# untitled2-6-2.net
KiCad netlist of a schematic drawn in EAGLE
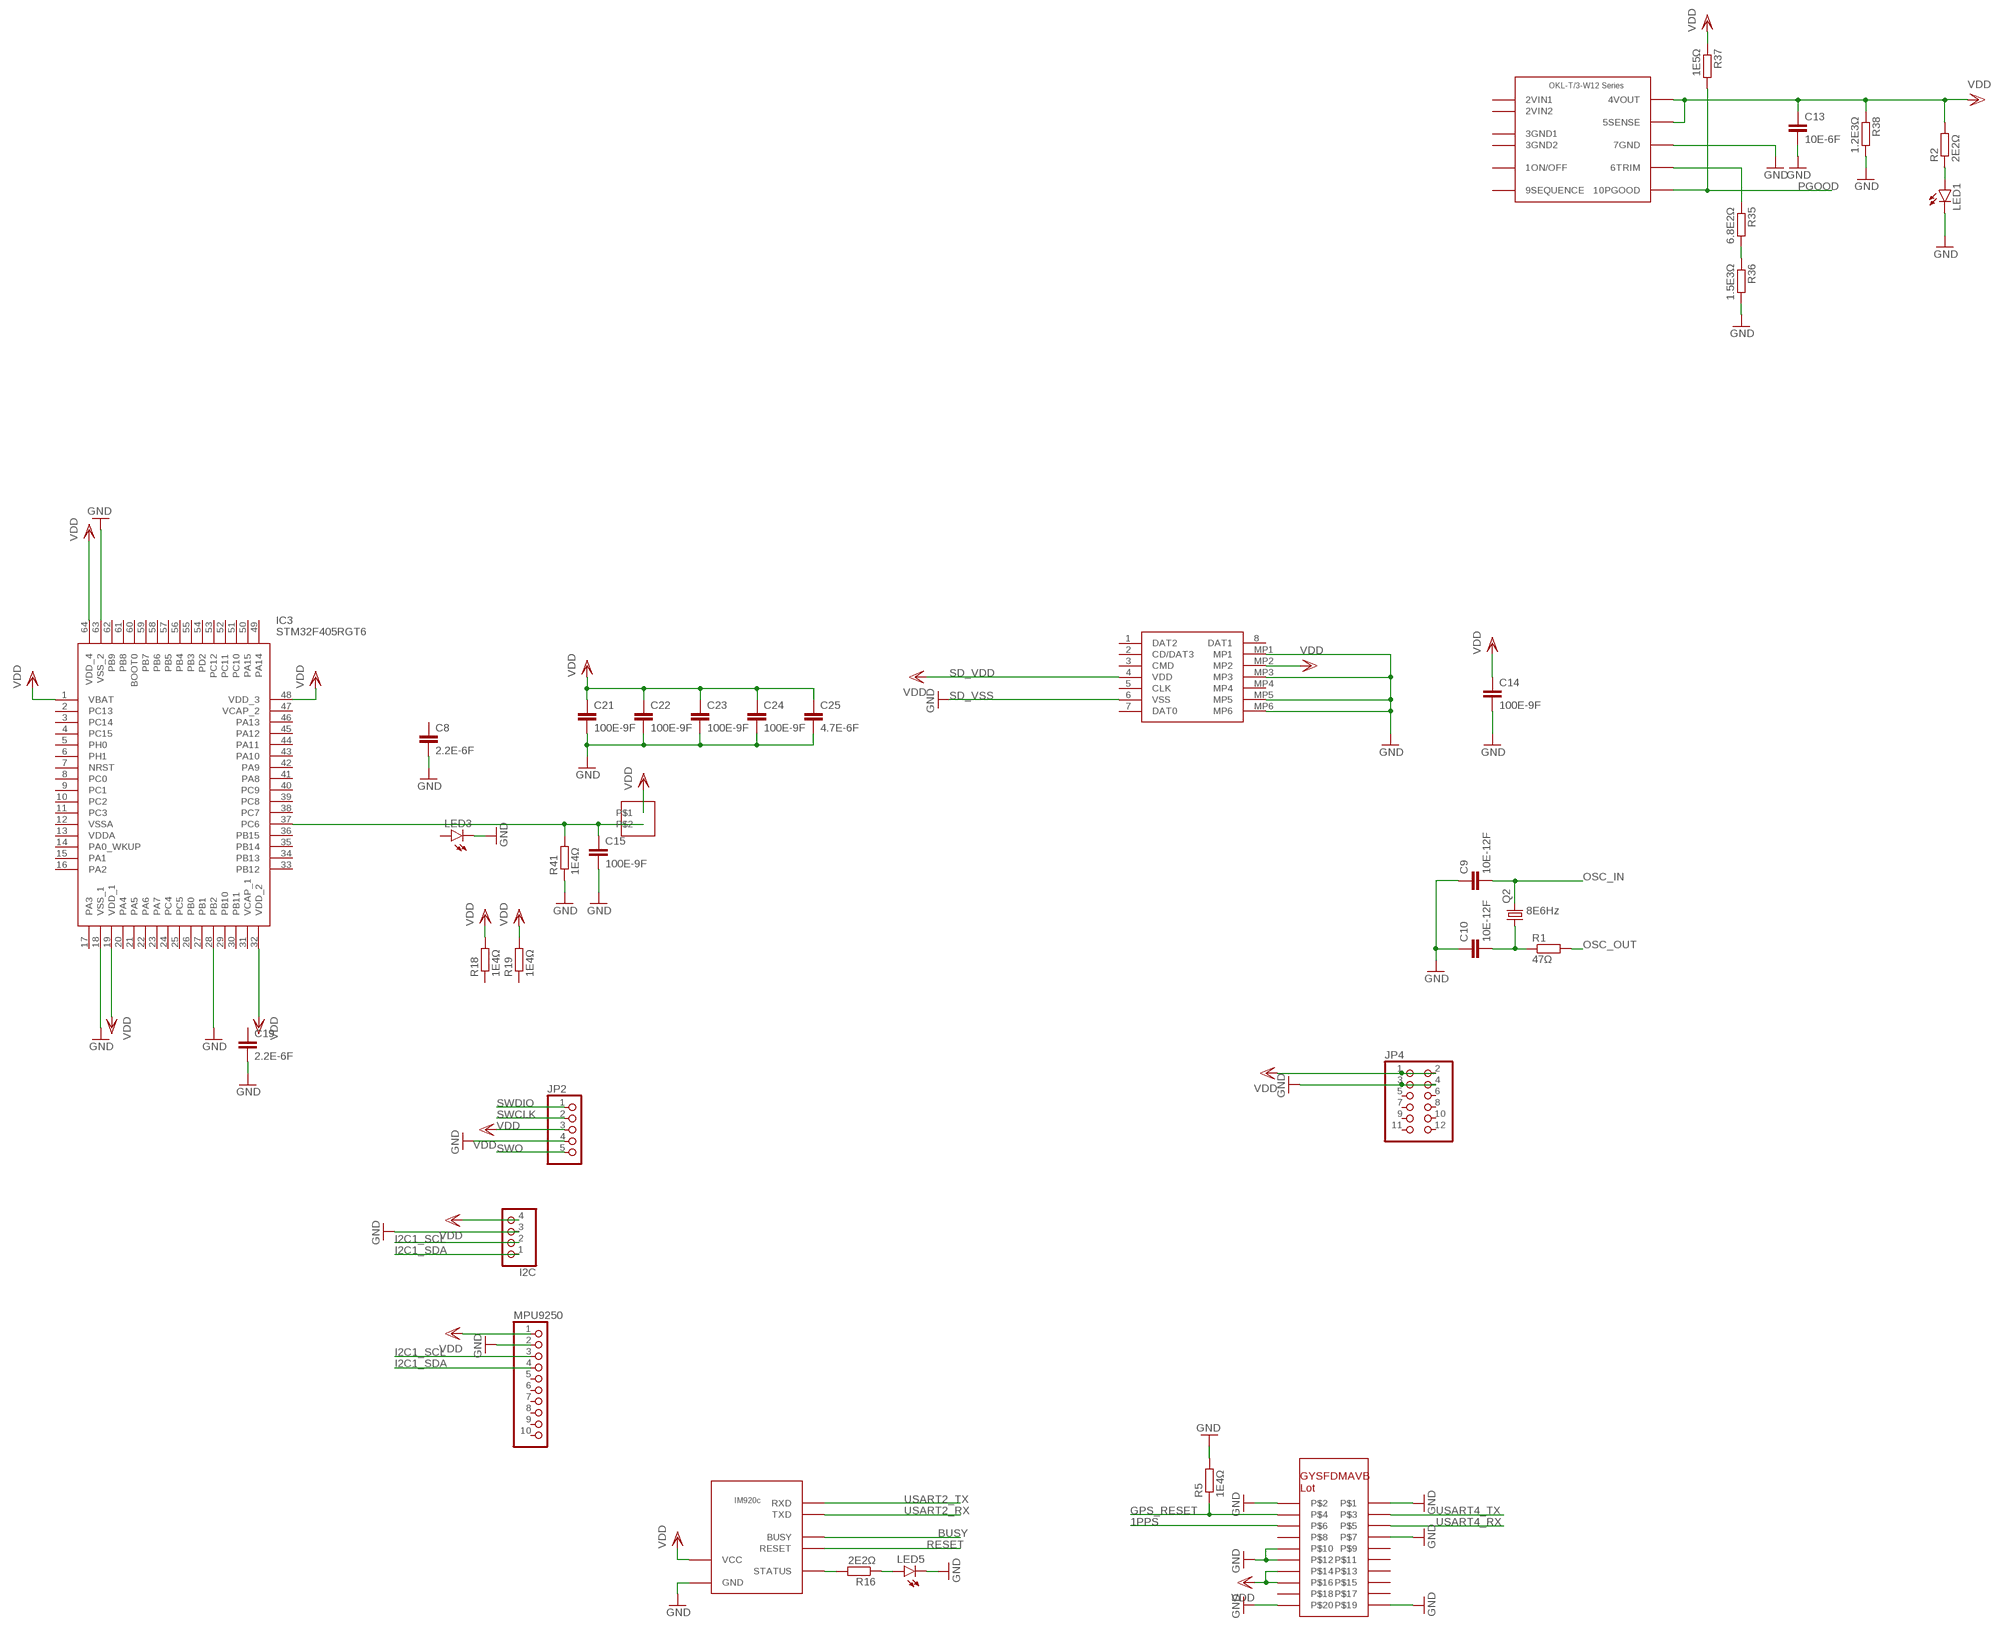
[diagram p0: schematic, sheet 1]

(export (version "E")
  (design (tool "Eeschema 10.0.6"))
  (components
    (comp (ref "C8")
      (value "2.2E-6F")
      (footprint "eagle-import:C0805")
      (libsource (lib "eagle-import") (part "C-EUC0805"))
    )
    (comp (ref "C9")
      (value "10E-12F")
      (footprint "eagle-import:C0805")
      (libsource (lib "eagle-import") (part "C-EUC0805"))
    )
    (comp (ref "C10")
      (value "10E-12F")
      (footprint "eagle-import:C0805")
      (libsource (lib "eagle-import") (part "C-EUC0805"))
    )
    (comp (ref "C13")
      (value "10E-6F")
      (footprint "eagle-import:C0805")
      (libsource (lib "eagle-import") (part "C-EUC0805"))
    )
    (comp (ref "C14")
      (value "100E-9F")
      (footprint "eagle-import:C0805")
      (libsource (lib "eagle-import") (part "C-EUC0805"))
    )
    (comp (ref "C15")
      (value "100E-9F")
      (footprint "eagle-import:C0805")
      (libsource (lib "eagle-import") (part "C-EUC0805"))
    )
    (comp (ref "C19")
      (value "2.2E-6F")
      (footprint "eagle-import:C0805")
      (libsource (lib "eagle-import") (part "C-EUC0805"))
    )
    (comp (ref "C21")
      (value "100E-9F")
      (footprint "eagle-import:C0805")
      (libsource (lib "eagle-import") (part "C-EUC0805"))
    )
    (comp (ref "C22")
      (value "100E-9F")
      (footprint "eagle-import:C0805")
      (libsource (lib "eagle-import") (part "C-EUC0805"))
    )
    (comp (ref "C23")
      (value "100E-9F")
      (footprint "eagle-import:C0805")
      (libsource (lib "eagle-import") (part "C-EUC0805"))
    )
    (comp (ref "C24")
      (value "100E-9F")
      (footprint "eagle-import:C0805")
      (libsource (lib "eagle-import") (part "C-EUC0805"))
    )
    (comp (ref "C25")
      (value "4.7E-6F")
      (footprint "eagle-import:C0805")
      (libsource (lib "eagle-import") (part "C-EUC0805"))
    )
    (comp (ref "I2C")
      (value "PINHD-1X4")
      (footprint "eagle-import:1X04")
      (libsource (lib "eagle-import") (part "PINHD-1X4"))
    )
    (comp (ref "IC3")
      (value "STM32F405RGT6")
      (footprint "eagle-import:QFP50P1200X1200X160-64N")
      (fields (field (name "MOUSER_PART_NUMBER") "511-STM32F405RGT6"))
      (libsource (lib "eagle-import") (part "STM32F405RGT6"))
    )
    (comp (ref "J1")
      (value "DM3AT-SF-PEJM5")
      (footprint "eagle-import:DM3ATSFPEJM5")
      (fields (field (name "MOUSER_PART_NUMBER") "798-DM3AT-SF-PEJM5"))
      (libsource (lib "eagle-import") (part "DM3AT-SF-PEJM5"))
    )
    (comp (ref "JP2")
      (value "PINHD-1X5")
      (footprint "eagle-import:1X05")
      (libsource (lib "eagle-import") (part "PINHD-1X5"))
    )
    (comp (ref "JP4")
      (value "PINHD-2X6")
      (footprint "eagle-import:2X06")
      (libsource (lib "eagle-import") (part "PINHD-2X6"))
    )
    (comp (ref "LED1")
      (value "LEDCHIP-LED0805")
      (footprint "eagle-import:CHIP-LED0805")
      (libsource (lib "eagle-import") (part "LEDCHIP-LED0805"))
    )
    (comp (ref "LED3")
      (value "LEDCHIP-LED0805")
      (footprint "eagle-import:CHIP-LED0805")
      (libsource (lib "eagle-import") (part "LEDCHIP-LED0805"))
    )
    (comp (ref "LED5")
      (value "LEDCHIP-LED0805")
      (footprint "eagle-import:CHIP-LED0805")
      (libsource (lib "eagle-import") (part "LEDCHIP-LED0805"))
    )
    (comp (ref "MPU9250")
      (value "PINHD-1X10")
      (footprint "eagle-import:1X10")
      (libsource (lib "eagle-import") (part "PINHD-1X10"))
    )
    (comp (ref "Q2")
      (value "CRYSTALCTS406")
      (footprint "eagle-import:CTS406")
      (libsource (lib "eagle-import") (part "CRYSTALCTS406"))
    )
    (comp (ref "R1")
      (value "47Ω")
      (footprint "eagle-import:R0603")
      (libsource (lib "eagle-import") (part "R-EU_R0603"))
    )
    (comp (ref "R2")
      (value "2E2Ω")
      (footprint "eagle-import:R0603")
      (libsource (lib "eagle-import") (part "R-EU_R0603"))
    )
    (comp (ref "R5")
      (value "1E4Ω")
      (footprint "eagle-import:R0603")
      (libsource (lib "eagle-import") (part "R-EU_R0603"))
    )
    (comp (ref "R16")
      (value "2E2Ω")
      (footprint "eagle-import:R0603")
      (libsource (lib "eagle-import") (part "R-EU_R0603"))
    )
    (comp (ref "R18")
      (value "1E4Ω")
      (footprint "eagle-import:R0603")
      (libsource (lib "eagle-import") (part "R-EU_R0603"))
    )
    (comp (ref "R19")
      (value "1E4Ω")
      (footprint "eagle-import:R0603")
      (libsource (lib "eagle-import") (part "R-EU_R0603"))
    )
    (comp (ref "R35")
      (value "6.8E2Ω")
      (footprint "eagle-import:R0603")
      (libsource (lib "eagle-import") (part "R-EU_R0603"))
    )
    (comp (ref "R36")
      (value "1.5E3Ω")
      (footprint "eagle-import:R0603")
      (libsource (lib "eagle-import") (part "R-EU_R0603"))
    )
    (comp (ref "R37")
      (value "1E5Ω")
      (footprint "eagle-import:R0603")
      (libsource (lib "eagle-import") (part "R-EU_R0603"))
    )
    (comp (ref "R38")
      (value "1.2E3Ω")
      (footprint "eagle-import:R0603")
      (libsource (lib "eagle-import") (part "R-EU_R0603"))
    )
    (comp (ref "R41")
      (value "1E4Ω")
      (footprint "eagle-import:R0603")
      (libsource (lib "eagle-import") (part "R-EU_R0603"))
    )
    (comp (ref "U$3")
      (value "OKL-T/3-W12SERIES")
      (footprint "eagle-import:OKL-T_3-W12SERIES")
      (libsource (lib "eagle-import") (part "OKL-T/3-W12SERIES"))
    )
    (comp (ref "U$4")
      (value "GYSFDMAXB_LOT")
      (footprint "eagle-import:GYSFDMAXB_LOT")
      (libsource (lib "eagle-import") (part "GYSFDMAXB_LOT"))
    )
    (comp (ref "U$5")
      (value "IM920C")
      (footprint "eagle-import:IM920C")
      (libsource (lib "eagle-import") (part "IM920C"))
    )
    (comp (ref "U$10")
      (value "B2B-XH-A")
      (footprint "eagle-import:B2B-XH-A")
      (libsource (lib "eagle-import") (part "B2B-XH-A"))
    )
  )
  (nets
    (net (code "1") (name "/1PPS") (class "Default")
      (node (ref "U$4") (pin "P$6") (pinfunction "P$6_P$6") (pintype "bidirectional"))
    )
    (net (code "2") (name "/BUSY") (class "Default")
      (node (ref "U$5") (pin "BUSY") (pinfunction "BUSY_BUSY") (pintype "bidirectional"))
    )
    (net (code "3") (name "/GPS_RESET") (class "Default")
      (node (ref "R5") (pin "1") (pinfunction "1_1") (pintype "passive"))
      (node (ref "U$4") (pin "P$4") (pinfunction "P$4_P$4") (pintype "bidirectional"))
    )
    (net (code "4") (name "/I2C1_SCL") (class "Default")
      (node (ref "I2C") (pin "2") (pinfunction "2_2") (pintype "passive"))
      (node (ref "MPU9250") (pin "3") (pinfunction "3_3") (pintype "passive"))
    )
    (net (code "5") (name "/I2C1_SDA") (class "Default")
      (node (ref "I2C") (pin "1") (pinfunction "1_1") (pintype "passive"))
      (node (ref "MPU9250") (pin "4") (pinfunction "4_4") (pintype "passive"))
    )
    (net (code "6") (name "/OSC_IN") (class "Default")
      (node (ref "C9") (pin "2") (pinfunction "2_2") (pintype "passive"))
      (node (ref "Q2") (pin "3") (pinfunction "2_3") (pintype "passive"))
    )
    (net (code "7") (name "/OSC_OUT") (class "Default")
      (node (ref "R1") (pin "2") (pinfunction "2_2") (pintype "passive"))
    )
    (net (code "8") (name "/PGOOD") (class "Default")
      (node (ref "R37") (pin "2") (pinfunction "2_2") (pintype "passive"))
      (node (ref "U$3") (pin "10PGOOD") (pinfunction "10PGOOD_10PGOOD") (pintype "bidirectional"))
    )
    (net (code "9") (name "/RESET") (class "Default")
      (node (ref "U$5") (pin "RESET") (pinfunction "RESET_RESET") (pintype "bidirectional"))
    )
    (net (code "10") (name "/SWCLK") (class "Default")
      (node (ref "JP2") (pin "2") (pinfunction "2_2") (pintype "passive"))
    )
    (net (code "11") (name "/SWDIO") (class "Default")
      (node (ref "JP2") (pin "1") (pinfunction "1_1") (pintype "passive"))
    )
    (net (code "12") (name "/SWO") (class "Default")
      (node (ref "JP2") (pin "5") (pinfunction "5_5") (pintype "passive"))
    )
    (net (code "13") (name "/USART2_RX") (class "Default")
      (node (ref "U$5") (pin "TXD") (pinfunction "TXD_TXD") (pintype "bidirectional"))
    )
    (net (code "14") (name "/USART2_TX") (class "Default")
      (node (ref "U$5") (pin "RXD") (pinfunction "RXD_RXD") (pintype "bidirectional"))
    )
    (net (code "15") (name "/USART4_RX") (class "Default")
      (node (ref "U$4") (pin "P$5") (pinfunction "P$5_P$5") (pintype "bidirectional"))
    )
    (net (code "16") (name "/USART4_TX") (class "Default")
      (node (ref "U$4") (pin "P$3") (pinfunction "P$3_P$3") (pintype "bidirectional"))
    )
    (net (code "17") (name "GND") (class "Default")
      (node (ref "C10") (pin "1") (pinfunction "1_1") (pintype "passive"))
      (node (ref "C13") (pin "2") (pinfunction "2_2") (pintype "passive"))
      (node (ref "C14") (pin "2") (pinfunction "2_2") (pintype "passive"))
      (node (ref "C15") (pin "2") (pinfunction "2_2") (pintype "passive"))
      (node (ref "C19") (pin "2") (pinfunction "2_2") (pintype "passive"))
      (node (ref "C21") (pin "2") (pinfunction "2_2") (pintype "passive"))
      (node (ref "C22") (pin "2") (pinfunction "2_2") (pintype "passive"))
      (node (ref "C23") (pin "2") (pinfunction "2_2") (pintype "passive"))
      (node (ref "C24") (pin "2") (pinfunction "2_2") (pintype "passive"))
      (node (ref "C25") (pin "2") (pinfunction "2_2") (pintype "passive"))
      (node (ref "C8") (pin "2") (pinfunction "2_2") (pintype "passive"))
      (node (ref "C9") (pin "1") (pinfunction "1_1") (pintype "passive"))
      (node (ref "I2C") (pin "3") (pinfunction "3_3") (pintype "passive"))
      (node (ref "IC3") (pin "18") (pinfunction "VSS_1_18") (pintype "bidirectional"))
      (node (ref "IC3") (pin "28") (pinfunction "PB2_28") (pintype "bidirectional"))
      (node (ref "IC3") (pin "63") (pinfunction "VSS_2_63") (pintype "bidirectional"))
      (node (ref "J1") (pin "6") (pinfunction "VSS_6") (pintype "bidirectional"))
      (node (ref "J1") (pin "MP1") (pinfunction "MP1_MP1") (pintype "bidirectional"))
      (node (ref "J1") (pin "MP3") (pinfunction "MP3_MP3") (pintype "bidirectional"))
      (node (ref "J1") (pin "MP5") (pinfunction "MP5_MP5") (pintype "bidirectional"))
      (node (ref "J1") (pin "MP6") (pinfunction "MP6_MP6") (pintype "bidirectional"))
      (node (ref "JP2") (pin "4") (pinfunction "4_4") (pintype "passive"))
      (node (ref "JP4") (pin "3") (pinfunction "3_3") (pintype "passive"))
      (node (ref "JP4") (pin "4") (pinfunction "4_4") (pintype "passive"))
      (node (ref "LED1") (pin "C") (pinfunction "C_C") (pintype "passive"))
      (node (ref "LED3") (pin "C") (pinfunction "C_C") (pintype "passive"))
      (node (ref "LED5") (pin "C") (pinfunction "C_C") (pintype "passive"))
      (node (ref "MPU9250") (pin "2") (pinfunction "2_2") (pintype "passive"))
      (node (ref "R36") (pin "2") (pinfunction "2_2") (pintype "passive"))
      (node (ref "R38") (pin "2") (pinfunction "2_2") (pintype "passive"))
      (node (ref "R41") (pin "1") (pinfunction "1_1") (pintype "passive"))
      (node (ref "R5") (pin "2") (pinfunction "2_2") (pintype "passive"))
      (node (ref "U$3") (pin "7GND") (pinfunction "7GND_7GND") (pintype "bidirectional"))
      (node (ref "U$4") (pin "P$1") (pinfunction "P$1_P$1") (pintype "bidirectional"))
      (node (ref "U$4") (pin "P$10") (pinfunction "P$10_P$10") (pintype "bidirectional"))
      (node (ref "U$4") (pin "P$12") (pinfunction "P$12_P$12") (pintype "bidirectional"))
      (node (ref "U$4") (pin "P$19") (pinfunction "P$19_P$19") (pintype "bidirectional"))
      (node (ref "U$4") (pin "P$2") (pinfunction "P$2_P$2") (pintype "bidirectional"))
      (node (ref "U$4") (pin "P$20") (pinfunction "P$20_P$20") (pintype "bidirectional"))
      (node (ref "U$4") (pin "P$7") (pinfunction "P$7_P$7") (pintype "bidirectional"))
      (node (ref "U$5") (pin "GND") (pinfunction "GND_GND") (pintype "bidirectional"))
    )
    (net (code "18") (name "Net-(C10-Pad2)") (class "Default")
      (node (ref "C10") (pin "2") (pinfunction "2_2") (pintype "passive"))
      (node (ref "Q2") (pin "1") (pinfunction "1_1") (pintype "passive"))
      (node (ref "R1") (pin "1") (pinfunction "1_1") (pintype "passive"))
    )
    (net (code "19") (name "Net-(IC3-PC6)") (class "Default")
      (node (ref "C15") (pin "1") (pinfunction "1_1") (pintype "passive"))
      (node (ref "IC3") (pin "37") (pinfunction "PC6_37") (pintype "bidirectional"))
      (node (ref "R41") (pin "2") (pinfunction "2_2") (pintype "passive"))
      (node (ref "U$10") (pin "P$2") (pinfunction "P$2_P$2") (pintype "bidirectional"))
    )
    (net (code "20") (name "Net-(LED1-PadA)") (class "Default")
      (node (ref "LED1") (pin "A") (pinfunction "A_A") (pintype "passive"))
      (node (ref "R2") (pin "1") (pinfunction "1_1") (pintype "passive"))
    )
    (net (code "21") (name "Net-(LED5-PadA)") (class "Default")
      (node (ref "LED5") (pin "A") (pinfunction "A_A") (pintype "passive"))
      (node (ref "R16") (pin "1") (pinfunction "1_1") (pintype "passive"))
    )
    (net (code "22") (name "Net-(R16-Pad2)") (class "Default")
      (node (ref "R16") (pin "2") (pinfunction "2_2") (pintype "passive"))
      (node (ref "U$5") (pin "STATUS") (pinfunction "STATUS_STATUS") (pintype "bidirectional"))
    )
    (net (code "23") (name "Net-(R35-Pad1)") (class "Default")
      (node (ref "R35") (pin "1") (pinfunction "1_1") (pintype "passive"))
      (node (ref "U$3") (pin "6TRIM") (pinfunction "6TRIM_6TRIM") (pintype "bidirectional"))
    )
    (net (code "24") (name "Net-(R35-Pad2)") (class "Default")
      (node (ref "R35") (pin "2") (pinfunction "2_2") (pintype "passive"))
      (node (ref "R36") (pin "1") (pinfunction "1_1") (pintype "passive"))
    )
    (net (code "25") (name "VDD") (class "Default")
      (node (ref "C13") (pin "1") (pinfunction "1_1") (pintype "passive"))
      (node (ref "C14") (pin "1") (pinfunction "1_1") (pintype "passive"))
      (node (ref "C21") (pin "1") (pinfunction "1_1") (pintype "passive"))
      (node (ref "C22") (pin "1") (pinfunction "1_1") (pintype "passive"))
      (node (ref "C23") (pin "1") (pinfunction "1_1") (pintype "passive"))
      (node (ref "C24") (pin "1") (pinfunction "1_1") (pintype "passive"))
      (node (ref "C25") (pin "1") (pinfunction "1_1") (pintype "passive"))
      (node (ref "I2C") (pin "4") (pinfunction "4_4") (pintype "passive"))
      (node (ref "IC3") (pin "1") (pinfunction "VBAT_1") (pintype "bidirectional"))
      (node (ref "IC3") (pin "19") (pinfunction "VDD_1_19") (pintype "bidirectional"))
      (node (ref "IC3") (pin "32") (pinfunction "VDD_2_32") (pintype "bidirectional"))
      (node (ref "IC3") (pin "48") (pinfunction "VDD_3_48") (pintype "bidirectional"))
      (node (ref "IC3") (pin "64") (pinfunction "VDD_4_64") (pintype "bidirectional"))
      (node (ref "J1") (pin "4") (pinfunction "VDD_4") (pintype "bidirectional"))
      (node (ref "J1") (pin "MP2") (pinfunction "MP2_MP2") (pintype "bidirectional"))
      (node (ref "JP2") (pin "3") (pinfunction "3_3") (pintype "passive"))
      (node (ref "JP4") (pin "1") (pinfunction "1_1") (pintype "passive"))
      (node (ref "JP4") (pin "2") (pinfunction "2_2") (pintype "passive"))
      (node (ref "MPU9250") (pin "1") (pinfunction "1_1") (pintype "passive"))
      (node (ref "R18") (pin "2") (pinfunction "2_2") (pintype "passive"))
      (node (ref "R19") (pin "2") (pinfunction "2_2") (pintype "passive"))
      (node (ref "R2") (pin "2") (pinfunction "2_2") (pintype "passive"))
      (node (ref "R37") (pin "1") (pinfunction "1_1") (pintype "passive"))
      (node (ref "R38") (pin "1") (pinfunction "1_1") (pintype "passive"))
      (node (ref "U$10") (pin "P$1") (pinfunction "P$1_P$1") (pintype "bidirectional"))
      (node (ref "U$3") (pin "4VOUT") (pinfunction "4VOUT_4VOUT") (pintype "bidirectional"))
      (node (ref "U$3") (pin "5SENSE") (pinfunction "5SENSE_5SENSE") (pintype "bidirectional"))
      (node (ref "U$4") (pin "P$14") (pinfunction "P$14_P$14") (pintype "bidirectional"))
      (node (ref "U$4") (pin "P$16") (pinfunction "P$16_P$16") (pintype "bidirectional"))
      (node (ref "U$5") (pin "VCC") (pinfunction "VCC_VCC") (pintype "bidirectional"))
    )
    (net (code "26") (name "unconnected-(C8-Pad1)") (class "Default")
      (node (ref "C8") (pin "1") (pinfunction "1_1") (pintype "passive"))
    )
    (net (code "27") (name "unconnected-(C19-Pad1)") (class "Default")
      (node (ref "C19") (pin "1") (pinfunction "1_1") (pintype "passive"))
    )
    (net (code "28") (name "unconnected-(IC3-BOOT0-Pad60)") (class "Default")
      (node (ref "IC3") (pin "60") (pinfunction "BOOT0_60") (pintype "bidirectional"))
    )
    (net (code "29") (name "unconnected-(IC3-NRST-Pad7)") (class "Default")
      (node (ref "IC3") (pin "7") (pinfunction "NRST_7") (pintype "bidirectional"))
    )
    (net (code "30") (name "unconnected-(IC3-PA0_WKUP-Pad14)") (class "Default")
      (node (ref "IC3") (pin "14") (pinfunction "PA0_WKUP_14") (pintype "bidirectional"))
    )
    (net (code "31") (name "unconnected-(IC3-PA1-Pad15)") (class "Default")
      (node (ref "IC3") (pin "15") (pinfunction "PA1_15") (pintype "bidirectional"))
    )
    (net (code "32") (name "unconnected-(IC3-PA2-Pad16)") (class "Default")
      (node (ref "IC3") (pin "16") (pinfunction "PA2_16") (pintype "bidirectional"))
    )
    (net (code "33") (name "unconnected-(IC3-PA3-Pad17)") (class "Default")
      (node (ref "IC3") (pin "17") (pinfunction "PA3_17") (pintype "bidirectional"))
    )
    (net (code "34") (name "unconnected-(IC3-PA4-Pad20)") (class "Default")
      (node (ref "IC3") (pin "20") (pinfunction "PA4_20") (pintype "bidirectional"))
    )
    (net (code "35") (name "unconnected-(IC3-PA5-Pad21)") (class "Default")
      (node (ref "IC3") (pin "21") (pinfunction "PA5_21") (pintype "bidirectional"))
    )
    (net (code "36") (name "unconnected-(IC3-PA6-Pad22)") (class "Default")
      (node (ref "IC3") (pin "22") (pinfunction "PA6_22") (pintype "bidirectional"))
    )
    (net (code "37") (name "unconnected-(IC3-PA7-Pad23)") (class "Default")
      (node (ref "IC3") (pin "23") (pinfunction "PA7_23") (pintype "bidirectional"))
    )
    (net (code "38") (name "unconnected-(IC3-PA8-Pad41)") (class "Default")
      (node (ref "IC3") (pin "41") (pinfunction "PA8_41") (pintype "bidirectional"))
    )
    (net (code "39") (name "unconnected-(IC3-PA9-Pad42)") (class "Default")
      (node (ref "IC3") (pin "42") (pinfunction "PA9_42") (pintype "bidirectional"))
    )
    (net (code "40") (name "unconnected-(IC3-PA10-Pad43)") (class "Default")
      (node (ref "IC3") (pin "43") (pinfunction "PA10_43") (pintype "bidirectional"))
    )
    (net (code "41") (name "unconnected-(IC3-PA11-Pad44)") (class "Default")
      (node (ref "IC3") (pin "44") (pinfunction "PA11_44") (pintype "bidirectional"))
    )
    (net (code "42") (name "unconnected-(IC3-PA12-Pad45)") (class "Default")
      (node (ref "IC3") (pin "45") (pinfunction "PA12_45") (pintype "bidirectional"))
    )
    (net (code "43") (name "unconnected-(IC3-PA13-Pad46)") (class "Default")
      (node (ref "IC3") (pin "46") (pinfunction "PA13_46") (pintype "bidirectional"))
    )
    (net (code "44") (name "unconnected-(IC3-PA14-Pad49)") (class "Default")
      (node (ref "IC3") (pin "49") (pinfunction "PA14_49") (pintype "bidirectional"))
    )
    (net (code "45") (name "unconnected-(IC3-PA15-Pad50)") (class "Default")
      (node (ref "IC3") (pin "50") (pinfunction "PA15_50") (pintype "bidirectional"))
    )
    (net (code "46") (name "unconnected-(IC3-PB0-Pad26)") (class "Default")
      (node (ref "IC3") (pin "26") (pinfunction "PB0_26") (pintype "bidirectional"))
    )
    (net (code "47") (name "unconnected-(IC3-PB1-Pad27)") (class "Default")
      (node (ref "IC3") (pin "27") (pinfunction "PB1_27") (pintype "bidirectional"))
    )
    (net (code "48") (name "unconnected-(IC3-PB3-Pad55)") (class "Default")
      (node (ref "IC3") (pin "55") (pinfunction "PB3_55") (pintype "bidirectional"))
    )
    (net (code "49") (name "unconnected-(IC3-PB4-Pad56)") (class "Default")
      (node (ref "IC3") (pin "56") (pinfunction "PB4_56") (pintype "bidirectional"))
    )
    (net (code "50") (name "unconnected-(IC3-PB5-Pad57)") (class "Default")
      (node (ref "IC3") (pin "57") (pinfunction "PB5_57") (pintype "bidirectional"))
    )
    (net (code "51") (name "unconnected-(IC3-PB6-Pad58)") (class "Default")
      (node (ref "IC3") (pin "58") (pinfunction "PB6_58") (pintype "bidirectional"))
    )
    (net (code "52") (name "unconnected-(IC3-PB7-Pad59)") (class "Default")
      (node (ref "IC3") (pin "59") (pinfunction "PB7_59") (pintype "bidirectional"))
    )
    (net (code "53") (name "unconnected-(IC3-PB8-Pad61)") (class "Default")
      (node (ref "IC3") (pin "61") (pinfunction "PB8_61") (pintype "bidirectional"))
    )
    (net (code "54") (name "unconnected-(IC3-PB9-Pad62)") (class "Default")
      (node (ref "IC3") (pin "62") (pinfunction "PB9_62") (pintype "bidirectional"))
    )
    (net (code "55") (name "unconnected-(IC3-PB10-Pad29)") (class "Default")
      (node (ref "IC3") (pin "29") (pinfunction "PB10_29") (pintype "bidirectional"))
    )
    (net (code "56") (name "unconnected-(IC3-PB11-Pad30)") (class "Default")
      (node (ref "IC3") (pin "30") (pinfunction "PB11_30") (pintype "bidirectional"))
    )
    (net (code "57") (name "unconnected-(IC3-PB12-Pad33)") (class "Default")
      (node (ref "IC3") (pin "33") (pinfunction "PB12_33") (pintype "bidirectional"))
    )
    (net (code "58") (name "unconnected-(IC3-PB13-Pad34)") (class "Default")
      (node (ref "IC3") (pin "34") (pinfunction "PB13_34") (pintype "bidirectional"))
    )
    (net (code "59") (name "unconnected-(IC3-PB14-Pad35)") (class "Default")
      (node (ref "IC3") (pin "35") (pinfunction "PB14_35") (pintype "bidirectional"))
    )
    (net (code "60") (name "unconnected-(IC3-PB15-Pad36)") (class "Default")
      (node (ref "IC3") (pin "36") (pinfunction "PB15_36") (pintype "bidirectional"))
    )
    (net (code "61") (name "unconnected-(IC3-PC0-Pad8)") (class "Default")
      (node (ref "IC3") (pin "8") (pinfunction "PC0_8") (pintype "bidirectional"))
    )
    (net (code "62") (name "unconnected-(IC3-PC1-Pad9)") (class "Default")
      (node (ref "IC3") (pin "9") (pinfunction "PC1_9") (pintype "bidirectional"))
    )
    (net (code "63") (name "unconnected-(IC3-PC2-Pad10)") (class "Default")
      (node (ref "IC3") (pin "10") (pinfunction "PC2_10") (pintype "bidirectional"))
    )
    (net (code "64") (name "unconnected-(IC3-PC3-Pad11)") (class "Default")
      (node (ref "IC3") (pin "11") (pinfunction "PC3_11") (pintype "bidirectional"))
    )
    (net (code "65") (name "unconnected-(IC3-PC4-Pad24)") (class "Default")
      (node (ref "IC3") (pin "24") (pinfunction "PC4_24") (pintype "bidirectional"))
    )
    (net (code "66") (name "unconnected-(IC3-PC5-Pad25)") (class "Default")
      (node (ref "IC3") (pin "25") (pinfunction "PC5_25") (pintype "bidirectional"))
    )
    (net (code "67") (name "unconnected-(IC3-PC7-Pad38)") (class "Default")
      (node (ref "IC3") (pin "38") (pinfunction "PC7_38") (pintype "bidirectional"))
    )
    (net (code "68") (name "unconnected-(IC3-PC8-Pad39)") (class "Default")
      (node (ref "IC3") (pin "39") (pinfunction "PC8_39") (pintype "bidirectional"))
    )
    (net (code "69") (name "unconnected-(IC3-PC9-Pad40)") (class "Default")
      (node (ref "IC3") (pin "40") (pinfunction "PC9_40") (pintype "bidirectional"))
    )
    (net (code "70") (name "unconnected-(IC3-PC10-Pad51)") (class "Default")
      (node (ref "IC3") (pin "51") (pinfunction "PC10_51") (pintype "bidirectional"))
    )
    (net (code "71") (name "unconnected-(IC3-PC11-Pad52)") (class "Default")
      (node (ref "IC3") (pin "52") (pinfunction "PC11_52") (pintype "bidirectional"))
    )
    (net (code "72") (name "unconnected-(IC3-PC12-Pad53)") (class "Default")
      (node (ref "IC3") (pin "53") (pinfunction "PC12_53") (pintype "bidirectional"))
    )
    (net (code "73") (name "unconnected-(IC3-PC13-Pad2)") (class "Default")
      (node (ref "IC3") (pin "2") (pinfunction "PC13_2") (pintype "bidirectional"))
    )
    (net (code "74") (name "unconnected-(IC3-PC14-Pad3)") (class "Default")
      (node (ref "IC3") (pin "3") (pinfunction "PC14_3") (pintype "bidirectional"))
    )
    (net (code "75") (name "unconnected-(IC3-PC15-Pad4)") (class "Default")
      (node (ref "IC3") (pin "4") (pinfunction "PC15_4") (pintype "bidirectional"))
    )
    (net (code "76") (name "unconnected-(IC3-PD2-Pad54)") (class "Default")
      (node (ref "IC3") (pin "54") (pinfunction "PD2_54") (pintype "bidirectional"))
    )
    (net (code "77") (name "unconnected-(IC3-PH0-Pad5)") (class "Default")
      (node (ref "IC3") (pin "5") (pinfunction "PH0_5") (pintype "bidirectional"))
    )
    (net (code "78") (name "unconnected-(IC3-PH1-Pad6)") (class "Default")
      (node (ref "IC3") (pin "6") (pinfunction "PH1_6") (pintype "bidirectional"))
    )
    (net (code "79") (name "unconnected-(IC3-VCAP_1-Pad31)") (class "Default")
      (node (ref "IC3") (pin "31") (pinfunction "VCAP_1_31") (pintype "bidirectional"))
    )
    (net (code "80") (name "unconnected-(IC3-VCAP_2-Pad47)") (class "Default")
      (node (ref "IC3") (pin "47") (pinfunction "VCAP_2_47") (pintype "bidirectional"))
    )
    (net (code "81") (name "unconnected-(IC3-VDDA-Pad13)") (class "Default")
      (node (ref "IC3") (pin "13") (pinfunction "VDDA_13") (pintype "bidirectional"))
    )
    (net (code "82") (name "unconnected-(IC3-VSSA-Pad12)") (class "Default")
      (node (ref "IC3") (pin "12") (pinfunction "VSSA_12") (pintype "bidirectional"))
    )
    (net (code "83") (name "unconnected-(J1-CD{slash}DAT3-Pad2)") (class "Default")
      (node (ref "J1") (pin "2") (pinfunction "CD/DAT3_2") (pintype "bidirectional"))
    )
    (net (code "84") (name "unconnected-(J1-CLK-Pad5)") (class "Default")
      (node (ref "J1") (pin "5") (pinfunction "CLK_5") (pintype "bidirectional"))
    )
    (net (code "85") (name "unconnected-(J1-CMD-Pad3)") (class "Default")
      (node (ref "J1") (pin "3") (pinfunction "CMD_3") (pintype "bidirectional"))
    )
    (net (code "86") (name "unconnected-(J1-DAT0-Pad7)") (class "Default")
      (node (ref "J1") (pin "7") (pinfunction "DAT0_7") (pintype "bidirectional"))
    )
    (net (code "87") (name "unconnected-(J1-DAT1-Pad8)") (class "Default")
      (node (ref "J1") (pin "8") (pinfunction "DAT1_8") (pintype "bidirectional"))
    )
    (net (code "88") (name "unconnected-(J1-DAT2-Pad1)") (class "Default")
      (node (ref "J1") (pin "1") (pinfunction "DAT2_1") (pintype "bidirectional"))
    )
    (net (code "89") (name "unconnected-(J1-PadMP4)") (class "Default")
      (node (ref "J1") (pin "MP4") (pinfunction "MP4_MP4") (pintype "bidirectional"))
    )
    (net (code "90") (name "unconnected-(JP4-Pad5)") (class "Default")
      (node (ref "JP4") (pin "5") (pinfunction "5_5") (pintype "passive"))
    )
    (net (code "91") (name "unconnected-(JP4-Pad6)") (class "Default")
      (node (ref "JP4") (pin "6") (pinfunction "6_6") (pintype "passive"))
    )
    (net (code "92") (name "unconnected-(JP4-Pad7)") (class "Default")
      (node (ref "JP4") (pin "7") (pinfunction "7_7") (pintype "passive"))
    )
    (net (code "93") (name "unconnected-(JP4-Pad8)") (class "Default")
      (node (ref "JP4") (pin "8") (pinfunction "8_8") (pintype "passive"))
    )
    (net (code "94") (name "unconnected-(JP4-Pad9)") (class "Default")
      (node (ref "JP4") (pin "9") (pinfunction "9_9") (pintype "passive"))
    )
    (net (code "95") (name "unconnected-(JP4-Pad10)") (class "Default")
      (node (ref "JP4") (pin "10") (pinfunction "10_10") (pintype "passive"))
    )
    (net (code "96") (name "unconnected-(JP4-Pad11)") (class "Default")
      (node (ref "JP4") (pin "11") (pinfunction "11_11") (pintype "passive"))
    )
    (net (code "97") (name "unconnected-(JP4-Pad12)") (class "Default")
      (node (ref "JP4") (pin "12") (pinfunction "12_12") (pintype "passive"))
    )
    (net (code "98") (name "unconnected-(LED3-PadA)") (class "Default")
      (node (ref "LED3") (pin "A") (pinfunction "A_A") (pintype "passive"))
    )
    (net (code "99") (name "unconnected-(MPU9250-Pad5)") (class "Default")
      (node (ref "MPU9250") (pin "5") (pinfunction "5_5") (pintype "passive"))
    )
    (net (code "100") (name "unconnected-(MPU9250-Pad6)") (class "Default")
      (node (ref "MPU9250") (pin "6") (pinfunction "6_6") (pintype "passive"))
    )
    (net (code "101") (name "unconnected-(MPU9250-Pad7)") (class "Default")
      (node (ref "MPU9250") (pin "7") (pinfunction "7_7") (pintype "passive"))
    )
    (net (code "102") (name "unconnected-(MPU9250-Pad8)") (class "Default")
      (node (ref "MPU9250") (pin "8") (pinfunction "8_8") (pintype "passive"))
    )
    (net (code "103") (name "unconnected-(MPU9250-Pad9)") (class "Default")
      (node (ref "MPU9250") (pin "9") (pinfunction "9_9") (pintype "passive"))
    )
    (net (code "104") (name "unconnected-(MPU9250-Pad10)") (class "Default")
      (node (ref "MPU9250") (pin "10") (pinfunction "10_10") (pintype "passive"))
    )
    (net (code "105") (name "unconnected-(R18-Pad1)") (class "Default")
      (node (ref "R18") (pin "1") (pinfunction "1_1") (pintype "passive"))
    )
    (net (code "106") (name "unconnected-(R19-Pad1)") (class "Default")
      (node (ref "R19") (pin "1") (pinfunction "1_1") (pintype "passive"))
    )
    (net (code "107") (name "unconnected-(U$3-3GND2-Pad3TGND2)") (class "Default")
      (node (ref "U$3") (pin "3TGND2") (pinfunction "3GND2_3TGND2") (pintype "bidirectional"))
    )
    (net (code "108") (name "unconnected-(U$3-Pad1ON{slash}OFF)") (class "Default")
      (node (ref "U$3") (pin "1ON/OFF") (pinfunction "1ON/OFF_1ON/OFF") (pintype "bidirectional"))
    )
    (net (code "109") (name "unconnected-(U$3-Pad2VIN1)") (class "Default")
      (node (ref "U$3") (pin "2VIN1") (pinfunction "2VIN1_2VIN1") (pintype "bidirectional"))
    )
    (net (code "110") (name "unconnected-(U$3-Pad2VIN2)") (class "Default")
      (node (ref "U$3") (pin "2VIN2") (pinfunction "2VIN2_2VIN2") (pintype "bidirectional"))
    )
    (net (code "111") (name "unconnected-(U$3-Pad3GND1)") (class "Default")
      (node (ref "U$3") (pin "3GND1") (pinfunction "3GND1_3GND1") (pintype "bidirectional"))
    )
    (net (code "112") (name "unconnected-(U$3-Pad9SEQUENCE)") (class "Default")
      (node (ref "U$3") (pin "9SEQUENCE") (pinfunction "9SEQUENCE_9SEQUENCE") (pintype "bidirectional"))
    )
    (net (code "113") (name "unconnected-(U$4-PadP$8)") (class "Default")
      (node (ref "U$4") (pin "P$8") (pinfunction "P$8_P$8") (pintype "bidirectional"))
    )
    (net (code "114") (name "unconnected-(U$4-PadP$9)") (class "Default")
      (node (ref "U$4") (pin "P$9") (pinfunction "P$9_P$9") (pintype "bidirectional"))
    )
    (net (code "115") (name "unconnected-(U$4-PadP$11)") (class "Default")
      (node (ref "U$4") (pin "P$11") (pinfunction "P$11_P$11") (pintype "bidirectional"))
    )
    (net (code "116") (name "unconnected-(U$4-PadP$13)") (class "Default")
      (node (ref "U$4") (pin "P$13") (pinfunction "P$13_P$13") (pintype "bidirectional"))
    )
    (net (code "117") (name "unconnected-(U$4-PadP$15)") (class "Default")
      (node (ref "U$4") (pin "P$15") (pinfunction "P$15_P$15") (pintype "bidirectional"))
    )
    (net (code "118") (name "unconnected-(U$4-PadP$17)") (class "Default")
      (node (ref "U$4") (pin "P$17") (pinfunction "P$17_P$17") (pintype "bidirectional"))
    )
    (net (code "119") (name "unconnected-(U$4-PadP$18)") (class "Default")
      (node (ref "U$4") (pin "P$18") (pinfunction "P$18_P$18") (pintype "bidirectional"))
    )
  )
)
